# Micro_Schematic.net
KiCad netlist of a schematic drawn in Altium Designer
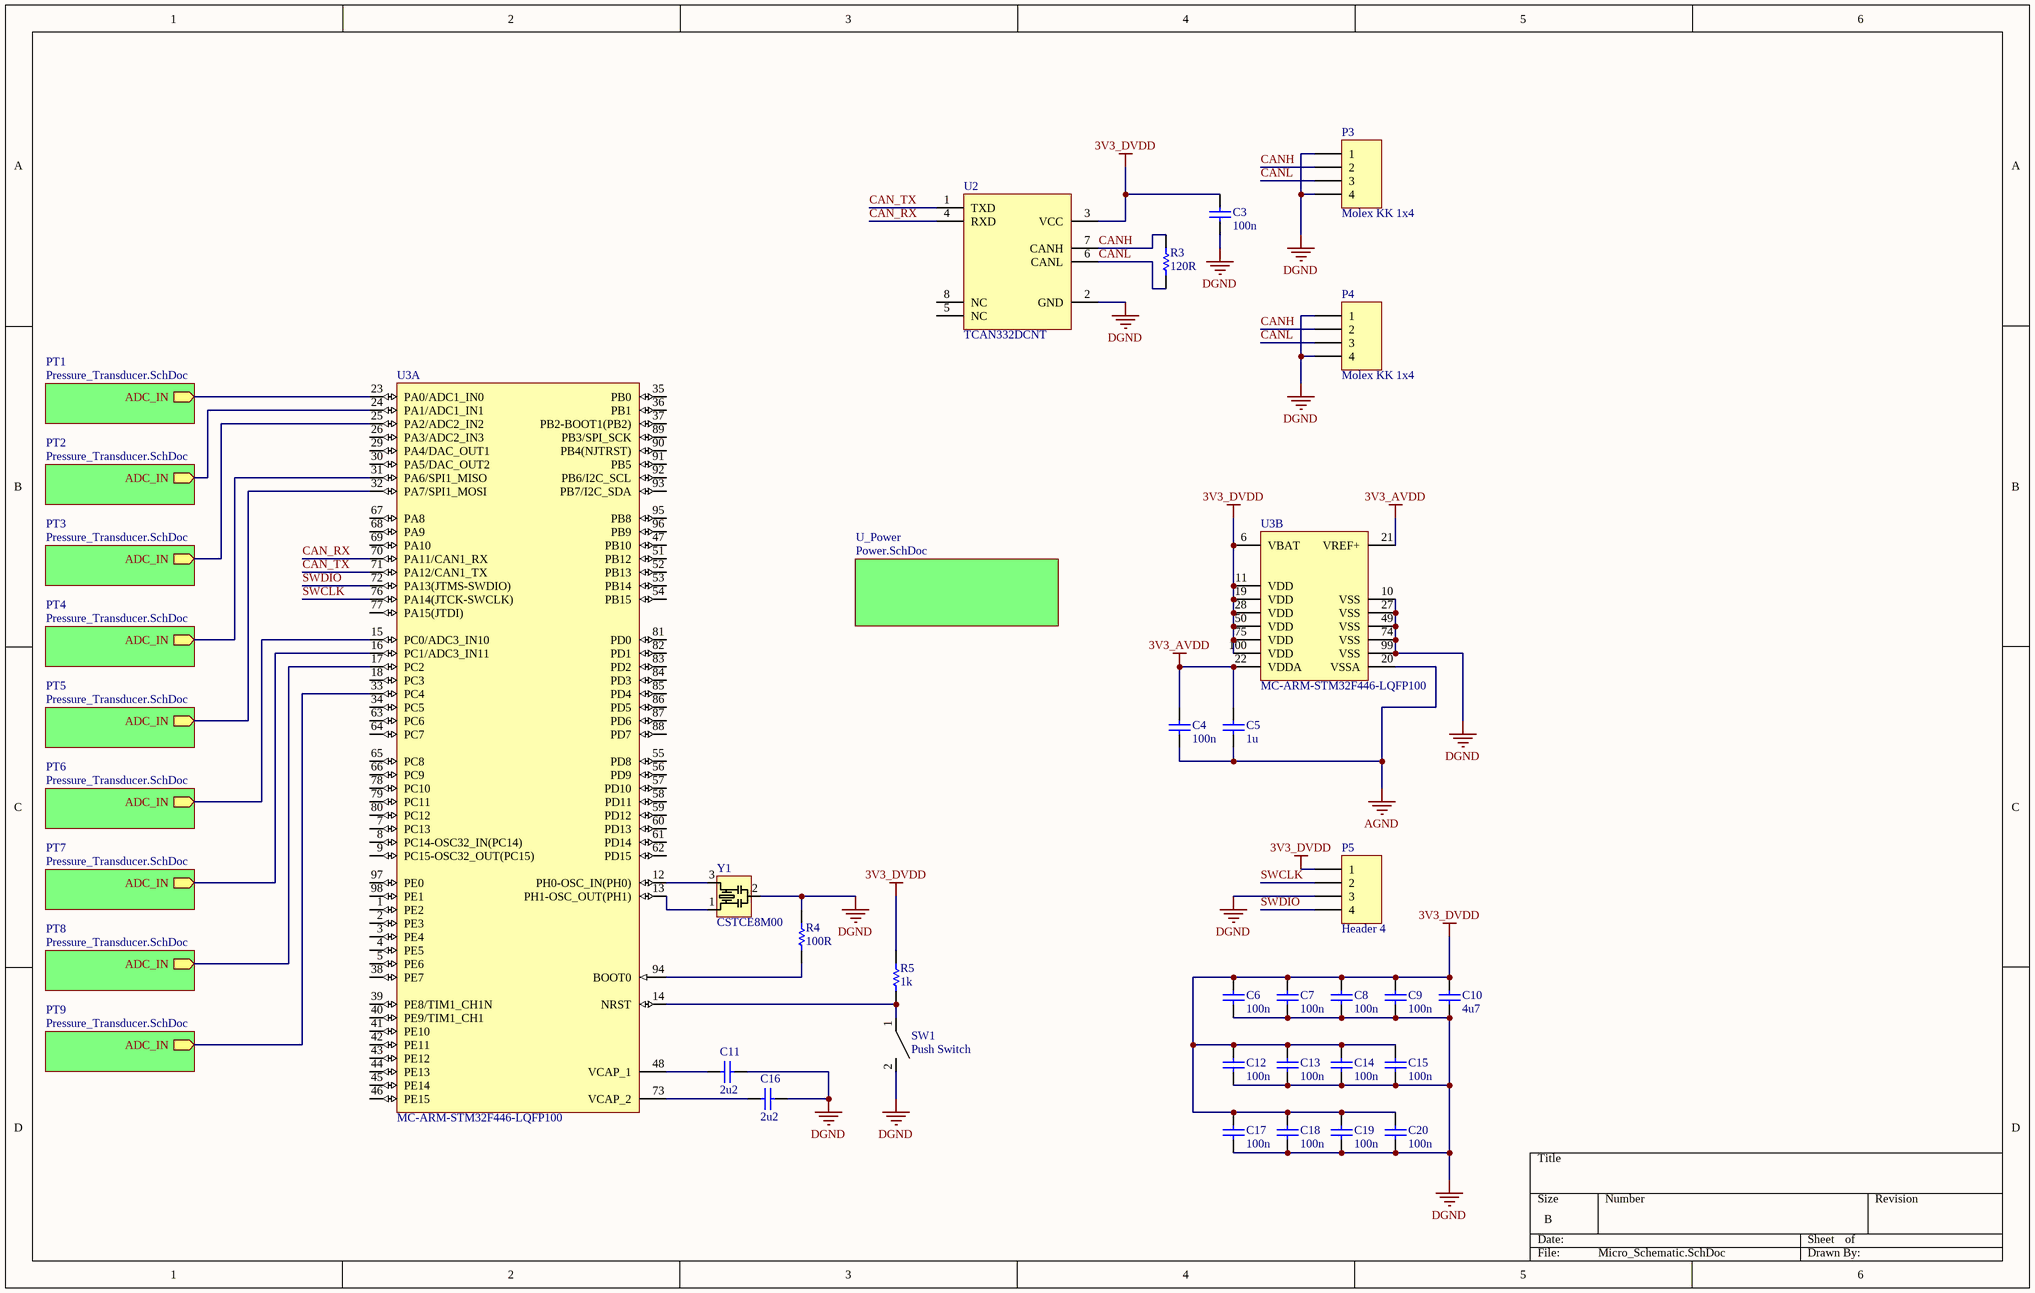
[diagram p0: Micro_Schematic.SchDoc]

(export (version "E")
  (design (tool "Eeschema 10.0.6"))
  (components
    (comp (ref "C3")
      (value "100n")
      (footprint "C0805")
      (description "0805 Capacitor")
      (libsource (lib "PARSEC") (part "C0805"))
    )
    (comp (ref "C4")
      (value "100n")
      (footprint "C0805")
      (description "0805 Capacitor")
      (libsource (lib "PARSEC") (part "C0805"))
    )
    (comp (ref "C5")
      (value "1u")
      (footprint "C0805")
      (description "0805 Capacitor")
      (libsource (lib "PARSEC") (part "C0805"))
    )
    (comp (ref "C6")
      (value "100n")
      (footprint "C0805")
      (description "0805 Capacitor")
      (libsource (lib "PARSEC") (part "C0805"))
    )
    (comp (ref "C7")
      (value "100n")
      (footprint "C0805")
      (description "0805 Capacitor")
      (libsource (lib "PARSEC") (part "C0805"))
    )
    (comp (ref "C8")
      (value "100n")
      (footprint "C0805")
      (description "0805 Capacitor")
      (libsource (lib "PARSEC") (part "C0805"))
    )
    (comp (ref "C9")
      (value "100n")
      (footprint "C0805")
      (description "0805 Capacitor")
      (libsource (lib "PARSEC") (part "C0805"))
    )
    (comp (ref "C10")
      (value "4u7")
      (footprint "C0805")
      (description "0805 Capacitor")
      (libsource (lib "PARSEC") (part "C0805"))
    )
    (comp (ref "C11")
      (value "2u2")
      (footprint "C0805")
      (description "0805 Capacitor")
      (libsource (lib "PARSEC") (part "C0805"))
    )
    (comp (ref "C12")
      (value "100n")
      (footprint "C0805")
      (description "0805 Capacitor")
      (libsource (lib "PARSEC") (part "C0805"))
    )
    (comp (ref "C13")
      (value "100n")
      (footprint "C0805")
      (description "0805 Capacitor")
      (libsource (lib "PARSEC") (part "C0805"))
    )
    (comp (ref "C14")
      (value "100n")
      (footprint "C0805")
      (description "0805 Capacitor")
      (libsource (lib "PARSEC") (part "C0805"))
    )
    (comp (ref "C15")
      (value "100n")
      (footprint "C0805")
      (description "0805 Capacitor")
      (libsource (lib "PARSEC") (part "C0805"))
    )
    (comp (ref "C16")
      (value "2u2")
      (footprint "C0805")
      (description "0805 Capacitor")
      (libsource (lib "PARSEC") (part "C0805"))
    )
    (comp (ref "C17")
      (value "100n")
      (footprint "C0805")
      (description "0805 Capacitor")
      (libsource (lib "PARSEC") (part "C0805"))
    )
    (comp (ref "C18")
      (value "100n")
      (footprint "C0805")
      (description "0805 Capacitor")
      (libsource (lib "PARSEC") (part "C0805"))
    )
    (comp (ref "C19")
      (value "100n")
      (footprint "C0805")
      (description "0805 Capacitor")
      (libsource (lib "PARSEC") (part "C0805"))
    )
    (comp (ref "C20")
      (value "100n")
      (footprint "C0805")
      (description "0805 Capacitor")
      (libsource (lib "PARSEC") (part "C0805"))
    )
    (comp (ref "P3")
      (value "Molex KK 1x4")
      (footprint "Molex KK 4x1")
      (description "1x4 Molex KK Connector")
      (libsource (lib "PARSEC") (part "Molex KK 1x4"))
    )
    (comp (ref "P4")
      (value "Molex KK 1x4")
      (footprint "Molex KK 4x1")
      (description "1x4 Molex KK Connector")
      (libsource (lib "PARSEC") (part "Molex KK 1x4"))
    )
    (comp (ref "P5")
      (value "Header 4")
      (footprint "HDR1X4")
      (description "Header, 4-Pin")
      (fields (field (name "PUBLISHER") "Altium Limited"))
      (libsource (lib "Miscellaneous Connectors") (part "Header 4"))
    )
    (comp (ref "R3")
      (value "120R")
      (footprint "R0805")
      (description "RESISTOR 0805")
      (libsource (lib "PARSEC") (part "R0805"))
    )
    (comp (ref "R4")
      (value "100R")
      (footprint "R0805")
      (description "RESISTOR 0805")
      (libsource (lib "PARSEC") (part "R0805"))
    )
    (comp (ref "R5")
      (value "1k")
      (footprint "R0805")
      (description "RESISTOR 0805")
      (libsource (lib "PARSEC") (part "R0805"))
    )
    (comp (ref "SW1")
      (value "Push Switch")
      (footprint "PUSHBUTTON")
      (libsource (lib "PARSEC") (part "PUSHBUTTON"))
    )
    (comp (ref "U2")
      (value "TCAN332DCNT")
      (footprint "SOT-23-8")
      (description "IC TXRX CAN 3.3V SOT23-8")
      (libsource (lib "PARSEC") (part "TCAN332DCNT"))
    )
    (comp (ref "U3")
      (value "MC-ARM-STM32F446-LQFP100")
      (footprint "STM-LQFP100_N")
      (libsource (lib "PARSEC") (part "MC-ARM-STM32F446-LQFP100"))
    )
    (comp (ref "Y1")
      (value "CSTCE8M00")
      (footprint "8MHz Ceramic Resonator")
      (description "8MHz Ceramic Resonator")
      (libsource (lib "PARSEC") (part "CSTCE8M00"))
    )
  )
  (nets
    (net (code "1") (name "/ADC_IN") (class "Default")
      (node (ref "U3") (pin "15") (pinfunction "PC0/ADC3_IN10_15") (pintype "bidirectional"))
    )
    (net (code "2") (name "/ADC_IN_1") (class "Default")
      (node (ref "U3") (pin "23") (pinfunction "PA0/ADC1_IN0_23") (pintype "bidirectional"))
    )
    (net (code "3") (name "/ADC_IN_2") (class "Default")
      (node (ref "U3") (pin "24") (pinfunction "PA1/ADC1_IN1_24") (pintype "bidirectional"))
    )
    (net (code "4") (name "/ADC_IN_3") (class "Default")
      (node (ref "U3") (pin "25") (pinfunction "PA2/ADC2_IN2_25") (pintype "bidirectional"))
    )
    (net (code "5") (name "/ADC_IN_4") (class "Default")
      (node (ref "U3") (pin "31") (pinfunction "PA6/SPI1_MISO_31") (pintype "bidirectional"))
    )
    (net (code "6") (name "/ADC_IN_5") (class "Default")
      (node (ref "U3") (pin "16") (pinfunction "PC1/ADC3_IN11_16") (pintype "bidirectional"))
    )
    (net (code "7") (name "/ADC_IN_6") (class "Default")
      (node (ref "U3") (pin "17") (pinfunction "PC2_17") (pintype "bidirectional"))
    )
    (net (code "8") (name "/ADC_IN_7") (class "Default")
      (node (ref "U3") (pin "33") (pinfunction "PC4_33") (pintype "bidirectional"))
    )
    (net (code "9") (name "/ADC_IN_8") (class "Default")
      (node (ref "U3") (pin "32") (pinfunction "PA7/SPI1_MOSI_32") (pintype "bidirectional"))
    )
    (net (code "10") (name "/CANH") (class "Default")
      (node (ref "P3") (pin "2") (pinfunction "2_2") (pintype "passive"))
      (node (ref "P4") (pin "2") (pinfunction "2_2") (pintype "passive"))
      (node (ref "R3") (pin "2") (pinfunction "2_2") (pintype "passive"))
      (node (ref "U2") (pin "7") (pinfunction "CANH_7") (pintype "passive"))
    )
    (net (code "11") (name "/CANL") (class "Default")
      (node (ref "P3") (pin "3") (pinfunction "3_3") (pintype "passive"))
      (node (ref "P4") (pin "3") (pinfunction "3_3") (pintype "passive"))
      (node (ref "R3") (pin "1") (pinfunction "1_1") (pintype "passive"))
      (node (ref "U2") (pin "6") (pinfunction "CANL_6") (pintype "passive"))
    )
    (net (code "12") (name "/CAN_RX") (class "Default")
      (node (ref "U2") (pin "4") (pinfunction "RXD_4") (pintype "passive"))
      (node (ref "U3") (pin "70") (pinfunction "PA11/CAN1_RX_70") (pintype "bidirectional"))
    )
    (net (code "13") (name "/CAN_TX") (class "Default")
      (node (ref "U2") (pin "1") (pinfunction "TXD_1") (pintype "passive"))
      (node (ref "U3") (pin "71") (pinfunction "PA12/CAN1_TX_71") (pintype "bidirectional"))
    )
    (net (code "14") (name "/SWCLK") (class "Default")
      (node (ref "P5") (pin "2") (pinfunction "2_2") (pintype "passive"))
      (node (ref "U3") (pin "76") (pinfunction "PA14(JTCK-SWCLK)_76") (pintype "bidirectional"))
    )
    (net (code "15") (name "/SWDIO") (class "Default")
      (node (ref "P5") (pin "4") (pinfunction "4_4") (pintype "passive"))
      (node (ref "U3") (pin "72") (pinfunction "PA13(JTMS-SWDIO)_72") (pintype "bidirectional"))
    )
    (net (code "16") (name "3V3_AVDD") (class "Default")
      (node (ref "C4") (pin "1") (pinfunction "1_1") (pintype "passive"))
      (node (ref "C5") (pin "1") (pinfunction "1_1") (pintype "passive"))
      (node (ref "U3") (pin "21") (pinfunction "VREF+_21") (pintype "power_in"))
      (node (ref "U3") (pin "22") (pinfunction "VDDA_22") (pintype "power_in"))
    )
    (net (code "17") (name "3V3_DVDD") (class "Default")
      (node (ref "C10") (pin "1") (pinfunction "1_1") (pintype "passive"))
      (node (ref "C12") (pin "1") (pinfunction "1_1") (pintype "passive"))
      (node (ref "C13") (pin "1") (pinfunction "1_1") (pintype "passive"))
      (node (ref "C14") (pin "1") (pinfunction "1_1") (pintype "passive"))
      (node (ref "C15") (pin "1") (pinfunction "1_1") (pintype "passive"))
      (node (ref "C17") (pin "1") (pinfunction "1_1") (pintype "passive"))
      (node (ref "C18") (pin "1") (pinfunction "1_1") (pintype "passive"))
      (node (ref "C19") (pin "1") (pinfunction "1_1") (pintype "passive"))
      (node (ref "C20") (pin "1") (pinfunction "1_1") (pintype "passive"))
      (node (ref "C3") (pin "1") (pinfunction "1_1") (pintype "passive"))
      (node (ref "C6") (pin "1") (pinfunction "1_1") (pintype "passive"))
      (node (ref "C7") (pin "1") (pinfunction "1_1") (pintype "passive"))
      (node (ref "C8") (pin "1") (pinfunction "1_1") (pintype "passive"))
      (node (ref "C9") (pin "1") (pinfunction "1_1") (pintype "passive"))
      (node (ref "P5") (pin "1") (pinfunction "1_1") (pintype "passive"))
      (node (ref "R5") (pin "2") (pinfunction "2_2") (pintype "passive"))
      (node (ref "U2") (pin "3") (pinfunction "VCC_3") (pintype "passive"))
      (node (ref "U3") (pin "100") (pinfunction "VDD_100") (pintype "power_in"))
      (node (ref "U3") (pin "11") (pinfunction "VDD_11") (pintype "power_in"))
      (node (ref "U3") (pin "19") (pinfunction "VDD_19") (pintype "power_in"))
      (node (ref "U3") (pin "28") (pinfunction "VDD_28") (pintype "power_in"))
      (node (ref "U3") (pin "50") (pinfunction "VDD_50") (pintype "power_in"))
      (node (ref "U3") (pin "6") (pinfunction "VBAT_6") (pintype "power_in"))
      (node (ref "U3") (pin "75") (pinfunction "VDD_75") (pintype "power_in"))
    )
    (net (code "18") (name "AGND") (class "Default")
      (node (ref "C4") (pin "2") (pinfunction "2_2") (pintype "passive"))
      (node (ref "C5") (pin "2") (pinfunction "2_2") (pintype "passive"))
      (node (ref "U3") (pin "20") (pinfunction "VSSA_20") (pintype "power_in"))
    )
    (net (code "19") (name "DGND") (class "Default")
      (node (ref "C10") (pin "2") (pinfunction "2_2") (pintype "passive"))
      (node (ref "C11") (pin "2") (pinfunction "2_2") (pintype "passive"))
      (node (ref "C12") (pin "2") (pinfunction "2_2") (pintype "passive"))
      (node (ref "C13") (pin "2") (pinfunction "2_2") (pintype "passive"))
      (node (ref "C14") (pin "2") (pinfunction "2_2") (pintype "passive"))
      (node (ref "C15") (pin "2") (pinfunction "2_2") (pintype "passive"))
      (node (ref "C16") (pin "2") (pinfunction "2_2") (pintype "passive"))
      (node (ref "C17") (pin "2") (pinfunction "2_2") (pintype "passive"))
      (node (ref "C18") (pin "2") (pinfunction "2_2") (pintype "passive"))
      (node (ref "C19") (pin "2") (pinfunction "2_2") (pintype "passive"))
      (node (ref "C20") (pin "2") (pinfunction "2_2") (pintype "passive"))
      (node (ref "C3") (pin "2") (pinfunction "2_2") (pintype "passive"))
      (node (ref "C6") (pin "2") (pinfunction "2_2") (pintype "passive"))
      (node (ref "C7") (pin "2") (pinfunction "2_2") (pintype "passive"))
      (node (ref "C8") (pin "2") (pinfunction "2_2") (pintype "passive"))
      (node (ref "C9") (pin "2") (pinfunction "2_2") (pintype "passive"))
      (node (ref "P3") (pin "1") (pinfunction "1_1") (pintype "passive"))
      (node (ref "P3") (pin "4") (pinfunction "4_4") (pintype "passive"))
      (node (ref "P4") (pin "1") (pinfunction "1_1") (pintype "passive"))
      (node (ref "P4") (pin "4") (pinfunction "4_4") (pintype "passive"))
      (node (ref "P5") (pin "3") (pinfunction "3_3") (pintype "passive"))
      (node (ref "R4") (pin "1") (pinfunction "1_1") (pintype "passive"))
      (node (ref "SW1") (pin "2") (pinfunction "1_2") (pintype "passive"))
      (node (ref "U2") (pin "2") (pinfunction "GND_2") (pintype "passive"))
      (node (ref "U3") (pin "10") (pinfunction "VSS_10") (pintype "power_in"))
      (node (ref "U3") (pin "27") (pinfunction "VSS_27") (pintype "power_in"))
      (node (ref "U3") (pin "49") (pinfunction "VSS_49") (pintype "power_in"))
      (node (ref "U3") (pin "74") (pinfunction "VSS_74") (pintype "power_in"))
      (node (ref "U3") (pin "99") (pinfunction "VSS_99") (pintype "power_in"))
      (node (ref "Y1") (pin "2") (pinfunction "GND_2") (pintype "passive"))
    )
    (net (code "20") (name "Net-(SW1-0)") (class "Default")
      (node (ref "R5") (pin "1") (pinfunction "1_1") (pintype "passive"))
      (node (ref "SW1") (pin "1") (pinfunction "0_1") (pintype "passive"))
      (node (ref "U3") (pin "14") (pinfunction "NRST_14") (pintype "bidirectional"))
    )
    (net (code "21") (name "Net-(U3A-BOOT0)") (class "Default")
      (node (ref "R4") (pin "2") (pinfunction "2_2") (pintype "passive"))
      (node (ref "U3") (pin "94") (pinfunction "BOOT0_94") (pintype "input"))
    )
    (net (code "22") (name "Net-(U3A-PH0-OSC_IN(PH0))") (class "Default")
      (node (ref "U3") (pin "12") (pinfunction "PH0-OSC_IN(PH0)_12") (pintype "bidirectional"))
      (node (ref "Y1") (pin "3") (pinfunction "OSC2_3") (pintype "passive"))
    )
    (net (code "23") (name "Net-(U3A-PH1-OSC_OUT(PH1))") (class "Default")
      (node (ref "U3") (pin "13") (pinfunction "PH1-OSC_OUT(PH1)_13") (pintype "bidirectional"))
      (node (ref "Y1") (pin "1") (pinfunction "OSC1_1") (pintype "passive"))
    )
    (net (code "24") (name "Net-(U3A-VCAP_1)") (class "Default")
      (node (ref "C11") (pin "1") (pinfunction "1_1") (pintype "passive"))
      (node (ref "U3") (pin "48") (pinfunction "VCAP_1_48") (pintype "passive"))
    )
    (net (code "25") (name "Net-(U3A-VCAP_2)") (class "Default")
      (node (ref "C16") (pin "1") (pinfunction "1_1") (pintype "passive"))
      (node (ref "U3") (pin "73") (pinfunction "VCAP_2_73") (pintype "passive"))
    )
    (net (code "26") (name "unconnected-(U2-NC-Pad5)") (class "Default")
      (node (ref "U2") (pin "5") (pinfunction "NC_5") (pintype "passive"))
    )
    (net (code "27") (name "unconnected-(U2-NC-Pad8)") (class "Default")
      (node (ref "U2") (pin "8") (pinfunction "NC_8") (pintype "passive"))
    )
    (net (code "28") (name "unconnected-(U3A-PA3{slash}ADC2_IN3-Pad26)") (class "Default")
      (node (ref "U3") (pin "26") (pinfunction "PA3/ADC2_IN3_26") (pintype "bidirectional"))
    )
    (net (code "29") (name "unconnected-(U3A-PA4{slash}DAC_OUT1-Pad29)") (class "Default")
      (node (ref "U3") (pin "29") (pinfunction "PA4/DAC_OUT1_29") (pintype "bidirectional"))
    )
    (net (code "30") (name "unconnected-(U3A-PA5{slash}DAC_OUT2-Pad30)") (class "Default")
      (node (ref "U3") (pin "30") (pinfunction "PA5/DAC_OUT2_30") (pintype "bidirectional"))
    )
    (net (code "31") (name "unconnected-(U3A-PA8-Pad67)") (class "Default")
      (node (ref "U3") (pin "67") (pinfunction "PA8_67") (pintype "bidirectional"))
    )
    (net (code "32") (name "unconnected-(U3A-PA9-Pad68)") (class "Default")
      (node (ref "U3") (pin "68") (pinfunction "PA9_68") (pintype "bidirectional"))
    )
    (net (code "33") (name "unconnected-(U3A-PA10-Pad69)") (class "Default")
      (node (ref "U3") (pin "69") (pinfunction "PA10_69") (pintype "bidirectional"))
    )
    (net (code "34") (name "unconnected-(U3A-PA15(JTDI)-Pad77)") (class "Default")
      (node (ref "U3") (pin "77") (pinfunction "PA15(JTDI)_77") (pintype "bidirectional"))
    )
    (net (code "35") (name "unconnected-(U3A-PB0-Pad35)") (class "Default")
      (node (ref "U3") (pin "35") (pinfunction "PB0_35") (pintype "bidirectional"))
    )
    (net (code "36") (name "unconnected-(U3A-PB1-Pad36)") (class "Default")
      (node (ref "U3") (pin "36") (pinfunction "PB1_36") (pintype "bidirectional"))
    )
    (net (code "37") (name "unconnected-(U3A-PB2-BOOT1(PB2)-Pad37)") (class "Default")
      (node (ref "U3") (pin "37") (pinfunction "PB2-BOOT1(PB2)_37") (pintype "bidirectional"))
    )
    (net (code "38") (name "unconnected-(U3A-PB3{slash}SPI_SCK-Pad89)") (class "Default")
      (node (ref "U3") (pin "89") (pinfunction "PB3/SPI_SCK_89") (pintype "bidirectional"))
    )
    (net (code "39") (name "unconnected-(U3A-PB4(NJTRST)-Pad90)") (class "Default")
      (node (ref "U3") (pin "90") (pinfunction "PB4(NJTRST)_90") (pintype "bidirectional"))
    )
    (net (code "40") (name "unconnected-(U3A-PB5-Pad91)") (class "Default")
      (node (ref "U3") (pin "91") (pinfunction "PB5_91") (pintype "bidirectional"))
    )
    (net (code "41") (name "unconnected-(U3A-PB6{slash}I2C_SCL-Pad92)") (class "Default")
      (node (ref "U3") (pin "92") (pinfunction "PB6/I2C_SCL_92") (pintype "bidirectional"))
    )
    (net (code "42") (name "unconnected-(U3A-PB7{slash}I2C_SDA-Pad93)") (class "Default")
      (node (ref "U3") (pin "93") (pinfunction "PB7/I2C_SDA_93") (pintype "bidirectional"))
    )
    (net (code "43") (name "unconnected-(U3A-PB8-Pad95)") (class "Default")
      (node (ref "U3") (pin "95") (pinfunction "PB8_95") (pintype "bidirectional"))
    )
    (net (code "44") (name "unconnected-(U3A-PB9-Pad96)") (class "Default")
      (node (ref "U3") (pin "96") (pinfunction "PB9_96") (pintype "bidirectional"))
    )
    (net (code "45") (name "unconnected-(U3A-PB10-Pad47)") (class "Default")
      (node (ref "U3") (pin "47") (pinfunction "PB10_47") (pintype "bidirectional"))
    )
    (net (code "46") (name "unconnected-(U3A-PB12-Pad51)") (class "Default")
      (node (ref "U3") (pin "51") (pinfunction "PB12_51") (pintype "bidirectional"))
    )
    (net (code "47") (name "unconnected-(U3A-PB13-Pad52)") (class "Default")
      (node (ref "U3") (pin "52") (pinfunction "PB13_52") (pintype "bidirectional"))
    )
    (net (code "48") (name "unconnected-(U3A-PB14-Pad53)") (class "Default")
      (node (ref "U3") (pin "53") (pinfunction "PB14_53") (pintype "bidirectional"))
    )
    (net (code "49") (name "unconnected-(U3A-PB15-Pad54)") (class "Default")
      (node (ref "U3") (pin "54") (pinfunction "PB15_54") (pintype "bidirectional"))
    )
    (net (code "50") (name "unconnected-(U3A-PC3-Pad18)") (class "Default")
      (node (ref "U3") (pin "18") (pinfunction "PC3_18") (pintype "bidirectional"))
    )
    (net (code "51") (name "unconnected-(U3A-PC5-Pad34)") (class "Default")
      (node (ref "U3") (pin "34") (pinfunction "PC5_34") (pintype "bidirectional"))
    )
    (net (code "52") (name "unconnected-(U3A-PC6-Pad63)") (class "Default")
      (node (ref "U3") (pin "63") (pinfunction "PC6_63") (pintype "bidirectional"))
    )
    (net (code "53") (name "unconnected-(U3A-PC7-Pad64)") (class "Default")
      (node (ref "U3") (pin "64") (pinfunction "PC7_64") (pintype "bidirectional"))
    )
    (net (code "54") (name "unconnected-(U3A-PC8-Pad65)") (class "Default")
      (node (ref "U3") (pin "65") (pinfunction "PC8_65") (pintype "bidirectional"))
    )
    (net (code "55") (name "unconnected-(U3A-PC9-Pad66)") (class "Default")
      (node (ref "U3") (pin "66") (pinfunction "PC9_66") (pintype "bidirectional"))
    )
    (net (code "56") (name "unconnected-(U3A-PC10-Pad78)") (class "Default")
      (node (ref "U3") (pin "78") (pinfunction "PC10_78") (pintype "bidirectional"))
    )
    (net (code "57") (name "unconnected-(U3A-PC11-Pad79)") (class "Default")
      (node (ref "U3") (pin "79") (pinfunction "PC11_79") (pintype "bidirectional"))
    )
    (net (code "58") (name "unconnected-(U3A-PC12-Pad80)") (class "Default")
      (node (ref "U3") (pin "80") (pinfunction "PC12_80") (pintype "bidirectional"))
    )
    (net (code "59") (name "unconnected-(U3A-PC13-Pad7)") (class "Default")
      (node (ref "U3") (pin "7") (pinfunction "PC13_7") (pintype "bidirectional"))
    )
    (net (code "60") (name "unconnected-(U3A-PC14-OSC32_IN(PC14)-Pad8)") (class "Default")
      (node (ref "U3") (pin "8") (pinfunction "PC14-OSC32_IN(PC14)_8") (pintype "bidirectional"))
    )
    (net (code "61") (name "unconnected-(U3A-PC15-OSC32_OUT(PC15)-Pad9)") (class "Default")
      (node (ref "U3") (pin "9") (pinfunction "PC15-OSC32_OUT(PC15)_9") (pintype "bidirectional"))
    )
    (net (code "62") (name "unconnected-(U3A-PD0-Pad81)") (class "Default")
      (node (ref "U3") (pin "81") (pinfunction "PD0_81") (pintype "bidirectional"))
    )
    (net (code "63") (name "unconnected-(U3A-PD1-Pad82)") (class "Default")
      (node (ref "U3") (pin "82") (pinfunction "PD1_82") (pintype "bidirectional"))
    )
    (net (code "64") (name "unconnected-(U3A-PD2-Pad83)") (class "Default")
      (node (ref "U3") (pin "83") (pinfunction "PD2_83") (pintype "bidirectional"))
    )
    (net (code "65") (name "unconnected-(U3A-PD3-Pad84)") (class "Default")
      (node (ref "U3") (pin "84") (pinfunction "PD3_84") (pintype "bidirectional"))
    )
    (net (code "66") (name "unconnected-(U3A-PD4-Pad85)") (class "Default")
      (node (ref "U3") (pin "85") (pinfunction "PD4_85") (pintype "bidirectional"))
    )
    (net (code "67") (name "unconnected-(U3A-PD5-Pad86)") (class "Default")
      (node (ref "U3") (pin "86") (pinfunction "PD5_86") (pintype "bidirectional"))
    )
    (net (code "68") (name "unconnected-(U3A-PD6-Pad87)") (class "Default")
      (node (ref "U3") (pin "87") (pinfunction "PD6_87") (pintype "bidirectional"))
    )
    (net (code "69") (name "unconnected-(U3A-PD7-Pad88)") (class "Default")
      (node (ref "U3") (pin "88") (pinfunction "PD7_88") (pintype "bidirectional"))
    )
    (net (code "70") (name "unconnected-(U3A-PD8-Pad55)") (class "Default")
      (node (ref "U3") (pin "55") (pinfunction "PD8_55") (pintype "bidirectional"))
    )
    (net (code "71") (name "unconnected-(U3A-PD9-Pad56)") (class "Default")
      (node (ref "U3") (pin "56") (pinfunction "PD9_56") (pintype "bidirectional"))
    )
    (net (code "72") (name "unconnected-(U3A-PD10-Pad57)") (class "Default")
      (node (ref "U3") (pin "57") (pinfunction "PD10_57") (pintype "bidirectional"))
    )
    (net (code "73") (name "unconnected-(U3A-PD11-Pad58)") (class "Default")
      (node (ref "U3") (pin "58") (pinfunction "PD11_58") (pintype "bidirectional"))
    )
    (net (code "74") (name "unconnected-(U3A-PD12-Pad59)") (class "Default")
      (node (ref "U3") (pin "59") (pinfunction "PD12_59") (pintype "bidirectional"))
    )
    (net (code "75") (name "unconnected-(U3A-PD13-Pad60)") (class "Default")
      (node (ref "U3") (pin "60") (pinfunction "PD13_60") (pintype "bidirectional"))
    )
    (net (code "76") (name "unconnected-(U3A-PD14-Pad61)") (class "Default")
      (node (ref "U3") (pin "61") (pinfunction "PD14_61") (pintype "bidirectional"))
    )
    (net (code "77") (name "unconnected-(U3A-PD15-Pad62)") (class "Default")
      (node (ref "U3") (pin "62") (pinfunction "PD15_62") (pintype "bidirectional"))
    )
    (net (code "78") (name "unconnected-(U3A-PE0-Pad97)") (class "Default")
      (node (ref "U3") (pin "97") (pinfunction "PE0_97") (pintype "bidirectional"))
    )
    (net (code "79") (name "unconnected-(U3A-PE1-Pad98)") (class "Default")
      (node (ref "U3") (pin "98") (pinfunction "PE1_98") (pintype "bidirectional"))
    )
    (net (code "80") (name "unconnected-(U3A-PE2-Pad1)") (class "Default")
      (node (ref "U3") (pin "1") (pinfunction "PE2_1") (pintype "bidirectional"))
    )
    (net (code "81") (name "unconnected-(U3A-PE3-Pad2)") (class "Default")
      (node (ref "U3") (pin "2") (pinfunction "PE3_2") (pintype "bidirectional"))
    )
    (net (code "82") (name "unconnected-(U3A-PE4-Pad3)") (class "Default")
      (node (ref "U3") (pin "3") (pinfunction "PE4_3") (pintype "bidirectional"))
    )
    (net (code "83") (name "unconnected-(U3A-PE5-Pad4)") (class "Default")
      (node (ref "U3") (pin "4") (pinfunction "PE5_4") (pintype "bidirectional"))
    )
    (net (code "84") (name "unconnected-(U3A-PE6-Pad5)") (class "Default")
      (node (ref "U3") (pin "5") (pinfunction "PE6_5") (pintype "bidirectional"))
    )
    (net (code "85") (name "unconnected-(U3A-PE7-Pad38)") (class "Default")
      (node (ref "U3") (pin "38") (pinfunction "PE7_38") (pintype "bidirectional"))
    )
    (net (code "86") (name "unconnected-(U3A-PE8{slash}TIM1_CH1N-Pad39)") (class "Default")
      (node (ref "U3") (pin "39") (pinfunction "PE8/TIM1_CH1N_39") (pintype "bidirectional"))
    )
    (net (code "87") (name "unconnected-(U3A-PE9{slash}TIM1_CH1-Pad40)") (class "Default")
      (node (ref "U3") (pin "40") (pinfunction "PE9/TIM1_CH1_40") (pintype "bidirectional"))
    )
    (net (code "88") (name "unconnected-(U3A-PE10-Pad41)") (class "Default")
      (node (ref "U3") (pin "41") (pinfunction "PE10_41") (pintype "bidirectional"))
    )
    (net (code "89") (name "unconnected-(U3A-PE11-Pad42)") (class "Default")
      (node (ref "U3") (pin "42") (pinfunction "PE11_42") (pintype "bidirectional"))
    )
    (net (code "90") (name "unconnected-(U3A-PE12-Pad43)") (class "Default")
      (node (ref "U3") (pin "43") (pinfunction "PE12_43") (pintype "bidirectional"))
    )
    (net (code "91") (name "unconnected-(U3A-PE13-Pad44)") (class "Default")
      (node (ref "U3") (pin "44") (pinfunction "PE13_44") (pintype "bidirectional"))
    )
    (net (code "92") (name "unconnected-(U3A-PE14-Pad45)") (class "Default")
      (node (ref "U3") (pin "45") (pinfunction "PE14_45") (pintype "bidirectional"))
    )
    (net (code "93") (name "unconnected-(U3A-PE15-Pad46)") (class "Default")
      (node (ref "U3") (pin "46") (pinfunction "PE15_46") (pintype "bidirectional"))
    )
  )
)
